# cnote.net
KiCad netlist of a schematic drawn in EAGLE
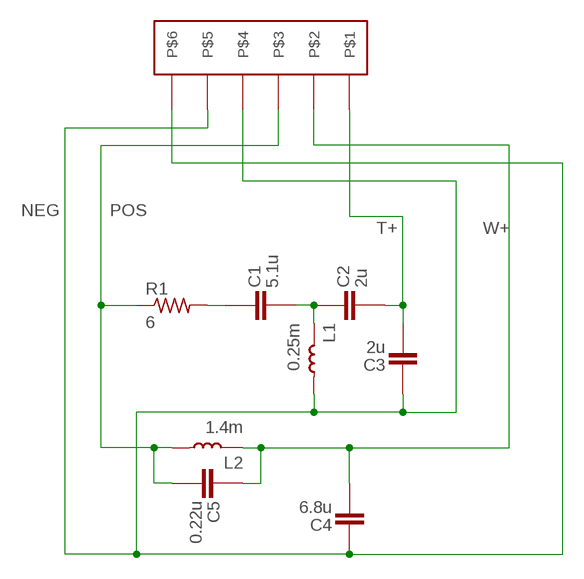
[diagram p0: schematic, sheet 1]

(export (version "E")
  (design (tool "Eeschema 10.0.6"))
  (components
    (comp (ref "C1")
      (value "5.1u")
      (footprint "eagle-import:DAYTON_21X31")
      (libsource (lib "eagle-import") (part "DAYTON_DMPC-5.1"))
    )
    (comp (ref "C2")
      (value "2u")
      (footprint "eagle-import:DAYTON_13X31")
      (libsource (lib "eagle-import") (part "DAYTON_DMPC-2.0"))
    )
    (comp (ref "C3")
      (value "2u")
      (footprint "eagle-import:DAYTON_13X31")
      (libsource (lib "eagle-import") (part "DAYTON_DMPC-2.0"))
    )
    (comp (ref "C4")
      (value "6.8u")
      (footprint "eagle-import:DAYTON_18X45")
      (libsource (lib "eagle-import") (part "DAYTON_DMPC-6.8"))
    )
    (comp (ref "C5")
      (value "0.22u")
      (footprint "eagle-import:DAYTON_7X18")
      (libsource (lib "eagle-import") (part "DAYTON_DMPC-0.22"))
    )
    (comp (ref "L1")
      (value "0.25m")
      (footprint "eagle-import:DAYTON_AC20-25")
      (libsource (lib "eagle-import") (part "DAYTON_AC20-25"))
    )
    (comp (ref "L2")
      (value "1.4m")
      (footprint "eagle-import:DAYTON_AC201-4")
      (libsource (lib "eagle-import") (part "DAYTON_AC201-4"))
    )
    (comp (ref "R1")
      (value "6")
      (footprint "eagle-import:DAYTON_48X10")
      (libsource (lib "eagle-import") (part "DAYTON_DNR-6.0"))
    )
    (comp (ref "U$1")
      (value "WURTH_WR-TBL-2416-6")
      (footprint "eagle-import:WURTH_WR-TBL-2416-6")
      (libsource (lib "eagle-import") (part "WURTH_WR-TBL-2416-6"))
    )
  )
  (nets
    (net (code "1") (name "/NEG") (class "Default")
      (node (ref "C3") (pin "P$1") (pinfunction "1_P$1") (pintype "passive"))
      (node (ref "C4") (pin "P$1") (pinfunction "1_P$1") (pintype "passive"))
      (node (ref "L1") (pin "P$1") (pinfunction "1_P$1") (pintype "passive"))
      (node (ref "U$1") (pin "P$4") (pinfunction "P$4_P$4") (pintype "bidirectional"))
      (node (ref "U$1") (pin "P$5") (pinfunction "P$5_P$5") (pintype "bidirectional"))
      (node (ref "U$1") (pin "P$6") (pinfunction "P$6_P$6") (pintype "bidirectional"))
    )
    (net (code "2") (name "/POS") (class "Default")
      (node (ref "C5") (pin "P$2") (pinfunction "2_P$2") (pintype "passive"))
      (node (ref "L2") (pin "P$1") (pinfunction "1_P$1") (pintype "passive"))
      (node (ref "R1") (pin "P$1") (pinfunction "1_P$1") (pintype "passive"))
      (node (ref "U$1") (pin "P$3") (pinfunction "P$3_P$3") (pintype "bidirectional"))
    )
    (net (code "3") (name "/T+") (class "Default")
      (node (ref "C2") (pin "P$2") (pinfunction "2_P$2") (pintype "passive"))
      (node (ref "C3") (pin "P$2") (pinfunction "2_P$2") (pintype "passive"))
      (node (ref "U$1") (pin "P$1") (pinfunction "P$1_P$1") (pintype "bidirectional"))
    )
    (net (code "4") (name "/W+") (class "Default")
      (node (ref "C4") (pin "P$2") (pinfunction "2_P$2") (pintype "passive"))
      (node (ref "C5") (pin "P$1") (pinfunction "1_P$1") (pintype "passive"))
      (node (ref "L2") (pin "P$2") (pinfunction "2_P$2") (pintype "passive"))
      (node (ref "U$1") (pin "P$2") (pinfunction "P$2_P$2") (pintype "bidirectional"))
    )
    (net (code "5") (name "Net-(C1-1)") (class "Default")
      (node (ref "C1") (pin "P$1") (pinfunction "1_P$1") (pintype "passive"))
      (node (ref "R1") (pin "P$2") (pinfunction "2_P$2") (pintype "passive"))
    )
    (net (code "6") (name "Net-(C1-2)") (class "Default")
      (node (ref "C1") (pin "P$2") (pinfunction "2_P$2") (pintype "passive"))
      (node (ref "C2") (pin "P$1") (pinfunction "1_P$1") (pintype "passive"))
      (node (ref "L1") (pin "P$2") (pinfunction "2_P$2") (pintype "passive"))
    )
  )
)
